# tsop_board.net
KiCad netlist of a schematic drawn in Altium Designer
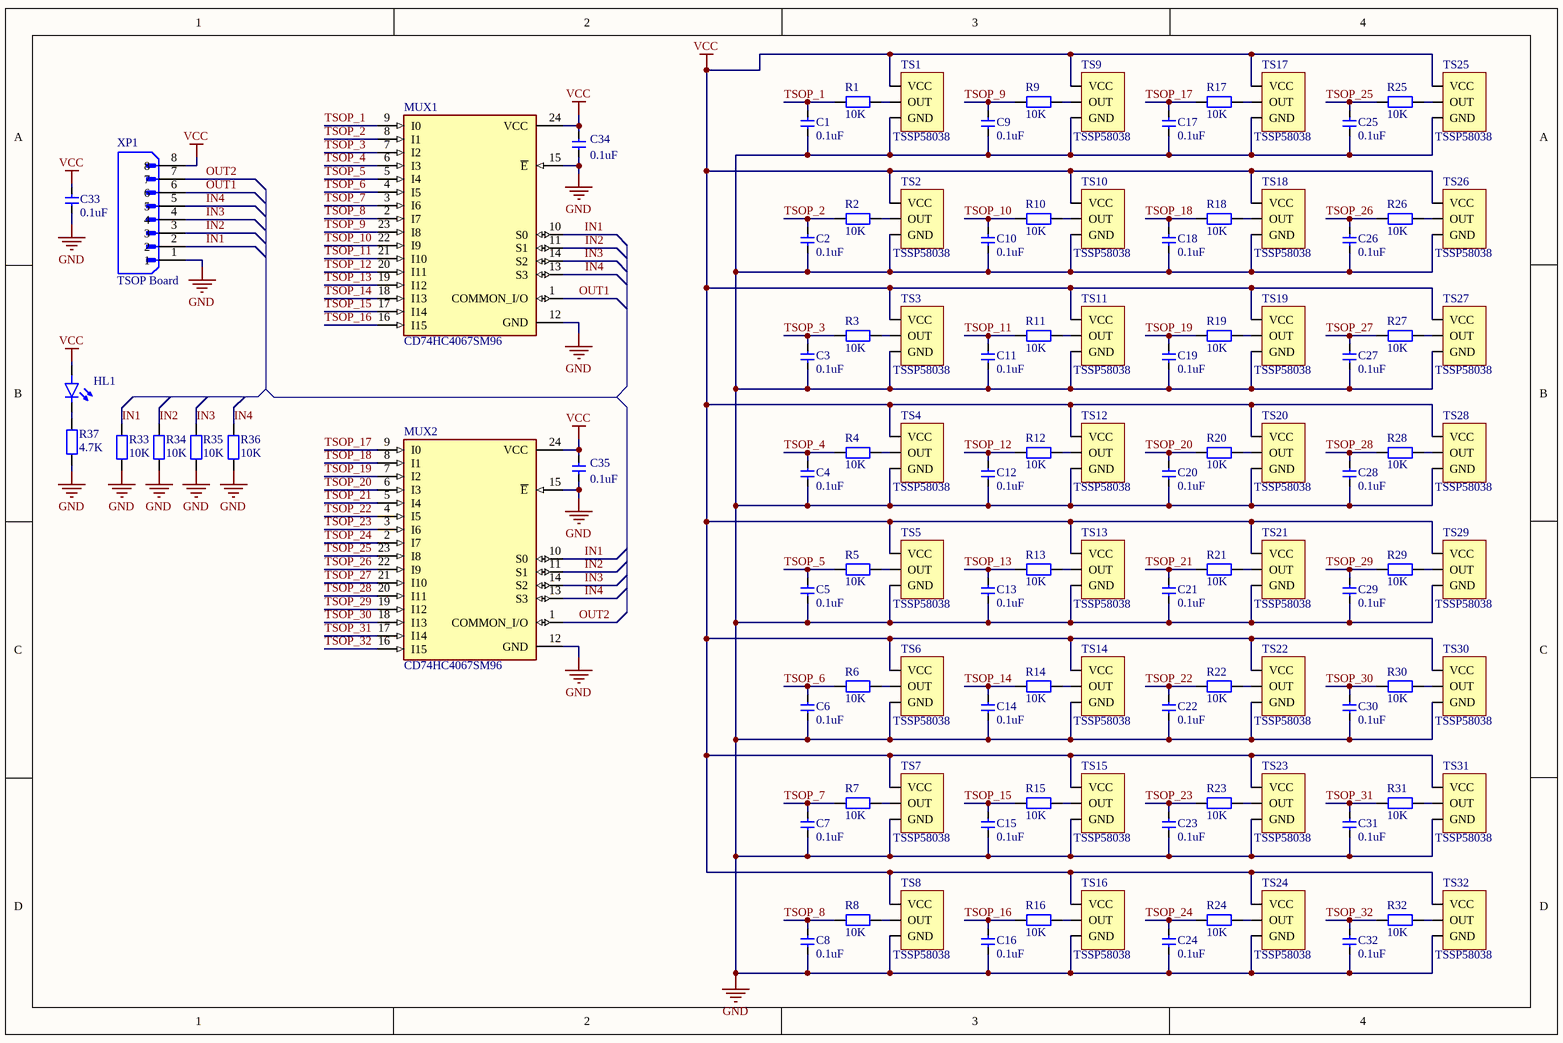
[diagram p0: tsop_board.SchDoc]

(export (version "E")
  (design (tool "Eeschema 10.0.6"))
  (components
    (comp (ref "C1")
      (value "0.1uF")
      (footprint "CAP0805")
      (description "Ceramic SMD Cap")
      (libsource (lib "Asterisk") (part "CAP Ceramic"))
    )
    (comp (ref "C2")
      (value "0.1uF")
      (footprint "CAP0805")
      (description "Ceramic SMD Cap")
      (libsource (lib "Asterisk") (part "CAP Ceramic"))
    )
    (comp (ref "C3")
      (value "0.1uF")
      (footprint "CAP0805")
      (description "Ceramic SMD Cap")
      (libsource (lib "Asterisk") (part "CAP Ceramic"))
    )
    (comp (ref "C4")
      (value "0.1uF")
      (footprint "CAP0805")
      (description "Ceramic SMD Cap")
      (libsource (lib "Asterisk") (part "CAP Ceramic"))
    )
    (comp (ref "C5")
      (value "0.1uF")
      (footprint "CAP0805")
      (description "Ceramic SMD Cap")
      (libsource (lib "Asterisk") (part "CAP Ceramic"))
    )
    (comp (ref "C6")
      (value "0.1uF")
      (footprint "CAP0805")
      (description "Ceramic SMD Cap")
      (libsource (lib "Asterisk") (part "CAP Ceramic"))
    )
    (comp (ref "C7")
      (value "0.1uF")
      (footprint "CAP0805")
      (description "Ceramic SMD Cap")
      (libsource (lib "Asterisk") (part "CAP Ceramic"))
    )
    (comp (ref "C8")
      (value "0.1uF")
      (footprint "CAP0805")
      (description "Ceramic SMD Cap")
      (libsource (lib "Asterisk") (part "CAP Ceramic"))
    )
    (comp (ref "C9")
      (value "0.1uF")
      (footprint "CAP0805")
      (description "Ceramic SMD Cap")
      (libsource (lib "Asterisk") (part "CAP Ceramic"))
    )
    (comp (ref "C10")
      (value "0.1uF")
      (footprint "CAP0805")
      (description "Ceramic SMD Cap")
      (libsource (lib "Asterisk") (part "CAP Ceramic"))
    )
    (comp (ref "C11")
      (value "0.1uF")
      (footprint "CAP0805")
      (description "Ceramic SMD Cap")
      (libsource (lib "Asterisk") (part "CAP Ceramic"))
    )
    (comp (ref "C12")
      (value "0.1uF")
      (footprint "CAP0805")
      (description "Ceramic SMD Cap")
      (libsource (lib "Asterisk") (part "CAP Ceramic"))
    )
    (comp (ref "C13")
      (value "0.1uF")
      (footprint "CAP0805")
      (description "Ceramic SMD Cap")
      (libsource (lib "Asterisk") (part "CAP Ceramic"))
    )
    (comp (ref "C14")
      (value "0.1uF")
      (footprint "CAP0805")
      (description "Ceramic SMD Cap")
      (libsource (lib "Asterisk") (part "CAP Ceramic"))
    )
    (comp (ref "C15")
      (value "0.1uF")
      (footprint "CAP0805")
      (description "Ceramic SMD Cap")
      (libsource (lib "Asterisk") (part "CAP Ceramic"))
    )
    (comp (ref "C16")
      (value "0.1uF")
      (footprint "CAP0805")
      (description "Ceramic SMD Cap")
      (libsource (lib "Asterisk") (part "CAP Ceramic"))
    )
    (comp (ref "C17")
      (value "0.1uF")
      (footprint "CAP0805")
      (description "Ceramic SMD Cap")
      (libsource (lib "Asterisk") (part "CAP Ceramic"))
    )
    (comp (ref "C18")
      (value "0.1uF")
      (footprint "CAP0805")
      (description "Ceramic SMD Cap")
      (libsource (lib "Asterisk") (part "CAP Ceramic"))
    )
    (comp (ref "C19")
      (value "0.1uF")
      (footprint "CAP0805")
      (description "Ceramic SMD Cap")
      (libsource (lib "Asterisk") (part "CAP Ceramic"))
    )
    (comp (ref "C20")
      (value "0.1uF")
      (footprint "CAP0805")
      (description "Ceramic SMD Cap")
      (libsource (lib "Asterisk") (part "CAP Ceramic"))
    )
    (comp (ref "C21")
      (value "0.1uF")
      (footprint "CAP0805")
      (description "Ceramic SMD Cap")
      (libsource (lib "Asterisk") (part "CAP Ceramic"))
    )
    (comp (ref "C22")
      (value "0.1uF")
      (footprint "CAP0805")
      (description "Ceramic SMD Cap")
      (libsource (lib "Asterisk") (part "CAP Ceramic"))
    )
    (comp (ref "C23")
      (value "0.1uF")
      (footprint "CAP0805")
      (description "Ceramic SMD Cap")
      (libsource (lib "Asterisk") (part "CAP Ceramic"))
    )
    (comp (ref "C24")
      (value "0.1uF")
      (footprint "CAP0805")
      (description "Ceramic SMD Cap")
      (libsource (lib "Asterisk") (part "CAP Ceramic"))
    )
    (comp (ref "C25")
      (value "0.1uF")
      (footprint "CAP0805")
      (description "Ceramic SMD Cap")
      (libsource (lib "Asterisk") (part "CAP Ceramic"))
    )
    (comp (ref "C26")
      (value "0.1uF")
      (footprint "CAP0805")
      (description "Ceramic SMD Cap")
      (libsource (lib "Asterisk") (part "CAP Ceramic"))
    )
    (comp (ref "C27")
      (value "0.1uF")
      (footprint "CAP0805")
      (description "Ceramic SMD Cap")
      (libsource (lib "Asterisk") (part "CAP Ceramic"))
    )
    (comp (ref "C28")
      (value "0.1uF")
      (footprint "CAP0805")
      (description "Ceramic SMD Cap")
      (libsource (lib "Asterisk") (part "CAP Ceramic"))
    )
    (comp (ref "C29")
      (value "0.1uF")
      (footprint "CAP0805")
      (description "Ceramic SMD Cap")
      (libsource (lib "Asterisk") (part "CAP Ceramic"))
    )
    (comp (ref "C30")
      (value "0.1uF")
      (footprint "CAP0805")
      (description "Ceramic SMD Cap")
      (libsource (lib "Asterisk") (part "CAP Ceramic"))
    )
    (comp (ref "C31")
      (value "0.1uF")
      (footprint "CAP0805")
      (description "Ceramic SMD Cap")
      (libsource (lib "Asterisk") (part "CAP Ceramic"))
    )
    (comp (ref "C32")
      (value "0.1uF")
      (footprint "CAP0805")
      (description "Ceramic SMD Cap")
      (libsource (lib "Asterisk") (part "CAP Ceramic"))
    )
    (comp (ref "C33")
      (value "0.1uF")
      (footprint "CAP0805")
      (description "Ceramic SMD Cap")
      (libsource (lib "Asterisk") (part "CAP Ceramic"))
    )
    (comp (ref "C34")
      (value "0.1uF")
      (footprint "CAP0805")
      (description "Ceramic SMD Cap")
      (libsource (lib "Asterisk") (part "CAP Ceramic"))
    )
    (comp (ref "C35")
      (value "0.1uF")
      (footprint "CAP0805")
      (description "Ceramic SMD Cap")
      (libsource (lib "Asterisk") (part "CAP Ceramic"))
    )
    (comp (ref "HL1")
      (value "VCC")
      (footprint "LED0603_GREEN")
      (description "LED smd")
      (libsource (lib "Asterisk") (part "LED"))
    )
    (comp (ref "MUX1")
      (value "CD74HC4067SM96")
      (footprint "SSOP-24")
      (description "16-channel multiplexer")
      (libsource (lib "Asterisk") (part "CD74HC4067SM96"))
    )
    (comp (ref "MUX2")
      (value "CD74HC4067SM96")
      (footprint "SSOP-24")
      (description "16-channel multiplexer")
      (libsource (lib "Asterisk") (part "CD74HC4067SM96"))
    )
    (comp (ref "R1")
      (value "10K")
      (footprint "RES0805")
      (description "RES smd")
      (libsource (lib "Asterisk") (part "RES"))
    )
    (comp (ref "R2")
      (value "10K")
      (footprint "RES0805")
      (description "RES smd")
      (libsource (lib "Asterisk") (part "RES"))
    )
    (comp (ref "R3")
      (value "10K")
      (footprint "RES0805")
      (description "RES smd")
      (libsource (lib "Asterisk") (part "RES"))
    )
    (comp (ref "R4")
      (value "10K")
      (footprint "RES0805")
      (description "RES smd")
      (libsource (lib "Asterisk") (part "RES"))
    )
    (comp (ref "R5")
      (value "10K")
      (footprint "RES0805")
      (description "RES smd")
      (libsource (lib "Asterisk") (part "RES"))
    )
    (comp (ref "R6")
      (value "10K")
      (footprint "RES0805")
      (description "RES smd")
      (libsource (lib "Asterisk") (part "RES"))
    )
    (comp (ref "R7")
      (value "10K")
      (footprint "RES0805")
      (description "RES smd")
      (libsource (lib "Asterisk") (part "RES"))
    )
    (comp (ref "R8")
      (value "10K")
      (footprint "RES0805")
      (description "RES smd")
      (libsource (lib "Asterisk") (part "RES"))
    )
    (comp (ref "R9")
      (value "10K")
      (footprint "RES0805")
      (description "RES smd")
      (libsource (lib "") (part "RES_1"))
    )
    (comp (ref "R10")
      (value "10K")
      (footprint "RES0805")
      (description "RES smd")
      (libsource (lib "") (part "RES_1"))
    )
    (comp (ref "R11")
      (value "10K")
      (footprint "RES0805")
      (description "RES smd")
      (libsource (lib "") (part "RES_1"))
    )
    (comp (ref "R12")
      (value "10K")
      (footprint "RES0805")
      (description "RES smd")
      (libsource (lib "") (part "RES_1"))
    )
    (comp (ref "R13")
      (value "10K")
      (footprint "RES0805")
      (description "RES smd")
      (libsource (lib "") (part "RES_1"))
    )
    (comp (ref "R14")
      (value "10K")
      (footprint "RES0805")
      (description "RES smd")
      (libsource (lib "") (part "RES_1"))
    )
    (comp (ref "R15")
      (value "10K")
      (footprint "RES0805")
      (description "RES smd")
      (libsource (lib "") (part "RES_1"))
    )
    (comp (ref "R16")
      (value "10K")
      (footprint "RES0805")
      (description "RES smd")
      (libsource (lib "") (part "RES_1"))
    )
    (comp (ref "R17")
      (value "10K")
      (footprint "RES0805")
      (description "RES smd")
      (libsource (lib "Asterisk") (part "RES"))
    )
    (comp (ref "R18")
      (value "10K")
      (footprint "RES0805")
      (description "RES smd")
      (libsource (lib "Asterisk") (part "RES"))
    )
    (comp (ref "R19")
      (value "10K")
      (footprint "RES0805")
      (description "RES smd")
      (libsource (lib "Asterisk") (part "RES"))
    )
    (comp (ref "R20")
      (value "10K")
      (footprint "RES0805")
      (description "RES smd")
      (libsource (lib "Asterisk") (part "RES"))
    )
    (comp (ref "R21")
      (value "10K")
      (footprint "RES0805")
      (description "RES smd")
      (libsource (lib "Asterisk") (part "RES"))
    )
    (comp (ref "R22")
      (value "10K")
      (footprint "RES0805")
      (description "RES smd")
      (libsource (lib "Asterisk") (part "RES"))
    )
    (comp (ref "R23")
      (value "10K")
      (footprint "RES0805")
      (description "RES smd")
      (libsource (lib "Asterisk") (part "RES"))
    )
    (comp (ref "R24")
      (value "10K")
      (footprint "RES0805")
      (description "RES smd")
      (libsource (lib "Asterisk") (part "RES"))
    )
    (comp (ref "R25")
      (value "10K")
      (footprint "RES0805")
      (description "RES smd")
      (libsource (lib "Asterisk") (part "RES"))
    )
    (comp (ref "R26")
      (value "10K")
      (footprint "RES0805")
      (description "RES smd")
      (libsource (lib "Asterisk") (part "RES"))
    )
    (comp (ref "R27")
      (value "10K")
      (footprint "RES0805")
      (description "RES smd")
      (libsource (lib "Asterisk") (part "RES"))
    )
    (comp (ref "R28")
      (value "10K")
      (footprint "RES0805")
      (description "RES smd")
      (libsource (lib "Asterisk") (part "RES"))
    )
    (comp (ref "R29")
      (value "10K")
      (footprint "RES0805")
      (description "RES smd")
      (libsource (lib "Asterisk") (part "RES"))
    )
    (comp (ref "R30")
      (value "10K")
      (footprint "RES0805")
      (description "RES smd")
      (libsource (lib "Asterisk") (part "RES"))
    )
    (comp (ref "R31")
      (value "10K")
      (footprint "RES0805")
      (description "RES smd")
      (libsource (lib "Asterisk") (part "RES"))
    )
    (comp (ref "R32")
      (value "10K")
      (footprint "RES0805")
      (description "RES smd")
      (libsource (lib "Asterisk") (part "RES"))
    )
    (comp (ref "R33")
      (value "10K")
      (footprint "RES0805")
      (description "RES smd")
      (libsource (lib "Asterisk") (part "RES"))
    )
    (comp (ref "R34")
      (value "10K")
      (footprint "RES0805")
      (description "RES smd")
      (libsource (lib "Asterisk") (part "RES"))
    )
    (comp (ref "R35")
      (value "10K")
      (footprint "RES0805")
      (description "RES smd")
      (libsource (lib "Asterisk") (part "RES"))
    )
    (comp (ref "R36")
      (value "10K")
      (footprint "RES0805")
      (description "RES smd")
      (libsource (lib "Asterisk") (part "RES"))
    )
    (comp (ref "R37")
      (value "4.7K")
      (footprint "RES0805")
      (description "RES smd")
      (libsource (lib "Asterisk") (part "RES"))
    )
    (comp (ref "TS1")
      (value "TSSP58038")
      (footprint "TSSP58038 (clear)")
      (description "TSOP TSSP58038")
      (libsource (lib "Asterisk") (part "TSSP58038"))
    )
    (comp (ref "TS2")
      (value "TSSP58038")
      (footprint "TSSP58038 (clear)")
      (description "TSOP TSSP58038")
      (libsource (lib "Asterisk") (part "TSSP58038"))
    )
    (comp (ref "TS3")
      (value "TSSP58038")
      (footprint "TSSP58038 (clear)")
      (description "TSOP TSSP58038")
      (libsource (lib "Asterisk") (part "TSSP58038"))
    )
    (comp (ref "TS4")
      (value "TSSP58038")
      (footprint "TSSP58038 (clear)")
      (description "TSOP TSSP58038")
      (libsource (lib "Asterisk") (part "TSSP58038"))
    )
    (comp (ref "TS5")
      (value "TSSP58038")
      (footprint "TSSP58038 (clear)")
      (description "TSOP TSSP58038")
      (libsource (lib "Asterisk") (part "TSSP58038"))
    )
    (comp (ref "TS6")
      (value "TSSP58038")
      (footprint "TSSP58038 (clear)")
      (description "TSOP TSSP58038")
      (libsource (lib "Asterisk") (part "TSSP58038"))
    )
    (comp (ref "TS7")
      (value "TSSP58038")
      (footprint "TSSP58038 (clear)")
      (description "TSOP TSSP58038")
      (libsource (lib "Asterisk") (part "TSSP58038"))
    )
    (comp (ref "TS8")
      (value "TSSP58038")
      (footprint "TSSP58038 (clear)")
      (description "TSOP TSSP58038")
      (libsource (lib "Asterisk") (part "TSSP58038"))
    )
    (comp (ref "TS9")
      (value "TSSP58038")
      (footprint "TSSP58038 (clear)")
      (description "TSOP TSSP58038")
      (libsource (lib "Asterisk") (part "TSSP58038"))
    )
    (comp (ref "TS10")
      (value "TSSP58038")
      (footprint "TSSP58038 (clear)")
      (description "TSOP TSSP58038")
      (libsource (lib "Asterisk") (part "TSSP58038"))
    )
    (comp (ref "TS11")
      (value "TSSP58038")
      (footprint "TSSP58038 (clear)")
      (description "TSOP TSSP58038")
      (libsource (lib "Asterisk") (part "TSSP58038"))
    )
    (comp (ref "TS12")
      (value "TSSP58038")
      (footprint "TSSP58038 (clear)")
      (description "TSOP TSSP58038")
      (libsource (lib "Asterisk") (part "TSSP58038"))
    )
    (comp (ref "TS13")
      (value "TSSP58038")
      (footprint "TSSP58038 (clear)")
      (description "TSOP TSSP58038")
      (libsource (lib "Asterisk") (part "TSSP58038"))
    )
    (comp (ref "TS14")
      (value "TSSP58038")
      (footprint "TSSP58038 (clear)")
      (description "TSOP TSSP58038")
      (libsource (lib "Asterisk") (part "TSSP58038"))
    )
    (comp (ref "TS15")
      (value "TSSP58038")
      (footprint "TSSP58038 (clear)")
      (description "TSOP TSSP58038")
      (libsource (lib "Asterisk") (part "TSSP58038"))
    )
    (comp (ref "TS16")
      (value "TSSP58038")
      (footprint "TSSP58038 (clear)")
      (description "TSOP TSSP58038")
      (libsource (lib "Asterisk") (part "TSSP58038"))
    )
    (comp (ref "TS17")
      (value "TSSP58038")
      (footprint "TSSP58038 (clear)")
      (description "TSOP TSSP58038")
      (libsource (lib "Asterisk") (part "TSSP58038"))
    )
    (comp (ref "TS18")
      (value "TSSP58038")
      (footprint "TSSP58038 (clear)")
      (description "TSOP TSSP58038")
      (libsource (lib "Asterisk") (part "TSSP58038"))
    )
    (comp (ref "TS19")
      (value "TSSP58038")
      (footprint "TSSP58038 (clear)")
      (description "TSOP TSSP58038")
      (libsource (lib "Asterisk") (part "TSSP58038"))
    )
    (comp (ref "TS20")
      (value "TSSP58038")
      (footprint "TSSP58038 (clear)")
      (description "TSOP TSSP58038")
      (libsource (lib "Asterisk") (part "TSSP58038"))
    )
    (comp (ref "TS21")
      (value "TSSP58038")
      (footprint "TSSP58038 (clear)")
      (description "TSOP TSSP58038")
      (libsource (lib "Asterisk") (part "TSSP58038"))
    )
    (comp (ref "TS22")
      (value "TSSP58038")
      (footprint "TSSP58038 (clear)")
      (description "TSOP TSSP58038")
      (libsource (lib "Asterisk") (part "TSSP58038"))
    )
    (comp (ref "TS23")
      (value "TSSP58038")
      (footprint "TSSP58038 (clear)")
      (description "TSOP TSSP58038")
      (libsource (lib "Asterisk") (part "TSSP58038"))
    )
    (comp (ref "TS24")
      (value "TSSP58038")
      (footprint "TSSP58038 (clear)")
      (description "TSOP TSSP58038")
      (libsource (lib "Asterisk") (part "TSSP58038"))
    )
    (comp (ref "TS25")
      (value "TSSP58038")
      (footprint "TSSP58038 (clear)")
      (description "TSOP TSSP58038")
      (libsource (lib "Asterisk") (part "TSSP58038"))
    )
    (comp (ref "TS26")
      (value "TSSP58038")
      (footprint "TSSP58038 (clear)")
      (description "TSOP TSSP58038")
      (libsource (lib "Asterisk") (part "TSSP58038"))
    )
    (comp (ref "TS27")
      (value "TSSP58038")
      (footprint "TSSP58038 (clear)")
      (description "TSOP TSSP58038")
      (libsource (lib "Asterisk") (part "TSSP58038"))
    )
    (comp (ref "TS28")
      (value "TSSP58038")
      (footprint "TSSP58038 (clear)")
      (description "TSOP TSSP58038")
      (libsource (lib "Asterisk") (part "TSSP58038"))
    )
    (comp (ref "TS29")
      (value "TSSP58038")
      (footprint "TSSP58038 (clear)")
      (description "TSOP TSSP58038")
      (libsource (lib "Asterisk") (part "TSSP58038"))
    )
    (comp (ref "TS30")
      (value "TSSP58038")
      (footprint "TSSP58038 (clear)")
      (description "TSOP TSSP58038")
      (libsource (lib "Asterisk") (part "TSSP58038"))
    )
    (comp (ref "TS31")
      (value "TSSP58038")
      (footprint "TSSP58038 (clear)")
      (description "TSOP TSSP58038")
      (libsource (lib "Asterisk") (part "TSSP58038"))
    )
    (comp (ref "TS32")
      (value "TSSP58038")
      (footprint "TSSP58038 (clear)")
      (description "TSOP TSSP58038")
      (libsource (lib "Asterisk") (part "TSSP58038"))
    )
    (comp (ref "XP1")
      (value "TSOP Board")
      (footprint "JST_XH-8")
      (description "JST_B8B-XH-A(LF)(SN)")
      (libsource (lib "Asterisk") (part "JST-XH-8"))
    )
  )
  (nets
    (net (code "1") (name "/IN1") (class "Default")
      (node (ref "MUX1") (pin "10") (pinfunction "S0_10") (pintype "bidirectional"))
      (node (ref "MUX2") (pin "10") (pinfunction "S0_10") (pintype "bidirectional"))
      (node (ref "R33") (pin "2") (pinfunction "2_2") (pintype "passive"))
      (node (ref "XP1") (pin "2") (pinfunction "2_2") (pintype "passive"))
    )
    (net (code "2") (name "/IN2") (class "Default")
      (node (ref "MUX1") (pin "11") (pinfunction "S1_11") (pintype "bidirectional"))
      (node (ref "MUX2") (pin "11") (pinfunction "S1_11") (pintype "bidirectional"))
      (node (ref "R34") (pin "2") (pinfunction "2_2") (pintype "passive"))
      (node (ref "XP1") (pin "3") (pinfunction "3_3") (pintype "passive"))
    )
    (net (code "3") (name "/IN3") (class "Default")
      (node (ref "MUX1") (pin "14") (pinfunction "S2_14") (pintype "bidirectional"))
      (node (ref "MUX2") (pin "14") (pinfunction "S2_14") (pintype "bidirectional"))
      (node (ref "R35") (pin "2") (pinfunction "2_2") (pintype "passive"))
      (node (ref "XP1") (pin "4") (pinfunction "4_4") (pintype "passive"))
    )
    (net (code "4") (name "/IN4") (class "Default")
      (node (ref "MUX1") (pin "13") (pinfunction "S3_13") (pintype "bidirectional"))
      (node (ref "MUX2") (pin "13") (pinfunction "S3_13") (pintype "bidirectional"))
      (node (ref "R36") (pin "2") (pinfunction "2_2") (pintype "passive"))
      (node (ref "XP1") (pin "5") (pinfunction "5_5") (pintype "passive"))
    )
    (net (code "5") (name "/OUT1") (class "Default")
      (node (ref "MUX1") (pin "1") (pinfunction "COMMON_I/O_1") (pintype "bidirectional"))
      (node (ref "XP1") (pin "6") (pinfunction "6_6") (pintype "passive"))
    )
    (net (code "6") (name "/OUT2") (class "Default")
      (node (ref "MUX2") (pin "1") (pinfunction "COMMON_I/O_1") (pintype "bidirectional"))
      (node (ref "XP1") (pin "7") (pinfunction "7_7") (pintype "passive"))
    )
    (net (code "7") (name "/TSOP_1") (class "Default")
      (node (ref "C1") (pin "2") (pinfunction "2_2") (pintype "passive"))
      (node (ref "MUX1") (pin "9") (pinfunction "I0_9") (pintype "input"))
      (node (ref "R1") (pin "1") (pinfunction "1_1") (pintype "passive"))
    )
    (net (code "8") (name "/TSOP_2") (class "Default")
      (node (ref "C2") (pin "2") (pinfunction "2_2") (pintype "passive"))
      (node (ref "MUX1") (pin "8") (pinfunction "I1_8") (pintype "input"))
      (node (ref "R2") (pin "1") (pinfunction "1_1") (pintype "passive"))
    )
    (net (code "9") (name "/TSOP_3") (class "Default")
      (node (ref "C3") (pin "2") (pinfunction "2_2") (pintype "passive"))
      (node (ref "MUX1") (pin "7") (pinfunction "I2_7") (pintype "input"))
      (node (ref "R3") (pin "1") (pinfunction "1_1") (pintype "passive"))
    )
    (net (code "10") (name "/TSOP_4") (class "Default")
      (node (ref "C4") (pin "2") (pinfunction "2_2") (pintype "passive"))
      (node (ref "MUX1") (pin "6") (pinfunction "I3_6") (pintype "input"))
      (node (ref "R4") (pin "1") (pinfunction "1_1") (pintype "passive"))
    )
    (net (code "11") (name "/TSOP_5") (class "Default")
      (node (ref "C5") (pin "2") (pinfunction "2_2") (pintype "passive"))
      (node (ref "MUX1") (pin "5") (pinfunction "I4_5") (pintype "input"))
      (node (ref "R5") (pin "1") (pinfunction "1_1") (pintype "passive"))
    )
    (net (code "12") (name "/TSOP_6") (class "Default")
      (node (ref "C6") (pin "2") (pinfunction "2_2") (pintype "passive"))
      (node (ref "MUX1") (pin "4") (pinfunction "I5_4") (pintype "input"))
      (node (ref "R6") (pin "1") (pinfunction "1_1") (pintype "passive"))
    )
    (net (code "13") (name "/TSOP_7") (class "Default")
      (node (ref "C7") (pin "2") (pinfunction "2_2") (pintype "passive"))
      (node (ref "MUX1") (pin "3") (pinfunction "I6_3") (pintype "input"))
      (node (ref "R7") (pin "1") (pinfunction "1_1") (pintype "passive"))
    )
    (net (code "14") (name "/TSOP_8") (class "Default")
      (node (ref "C8") (pin "2") (pinfunction "2_2") (pintype "passive"))
      (node (ref "MUX1") (pin "2") (pinfunction "I7_2") (pintype "input"))
      (node (ref "R8") (pin "1") (pinfunction "1_1") (pintype "passive"))
    )
    (net (code "15") (name "/TSOP_9") (class "Default")
      (node (ref "C9") (pin "2") (pinfunction "2_2") (pintype "passive"))
      (node (ref "MUX1") (pin "23") (pinfunction "I8_23") (pintype "input"))
      (node (ref "R9") (pin "1") (pinfunction "1_1") (pintype "passive"))
    )
    (net (code "16") (name "/TSOP_10") (class "Default")
      (node (ref "C10") (pin "2") (pinfunction "2_2") (pintype "passive"))
      (node (ref "MUX1") (pin "22") (pinfunction "I9_22") (pintype "input"))
      (node (ref "R10") (pin "1") (pinfunction "1_1") (pintype "passive"))
    )
    (net (code "17") (name "/TSOP_11") (class "Default")
      (node (ref "C11") (pin "2") (pinfunction "2_2") (pintype "passive"))
      (node (ref "MUX1") (pin "21") (pinfunction "I10_21") (pintype "input"))
      (node (ref "R11") (pin "1") (pinfunction "1_1") (pintype "passive"))
    )
    (net (code "18") (name "/TSOP_12") (class "Default")
      (node (ref "C12") (pin "2") (pinfunction "2_2") (pintype "passive"))
      (node (ref "MUX1") (pin "20") (pinfunction "I11_20") (pintype "input"))
      (node (ref "R12") (pin "1") (pinfunction "1_1") (pintype "passive"))
    )
    (net (code "19") (name "/TSOP_13") (class "Default")
      (node (ref "C13") (pin "2") (pinfunction "2_2") (pintype "passive"))
      (node (ref "MUX1") (pin "19") (pinfunction "I12_19") (pintype "input"))
      (node (ref "R13") (pin "1") (pinfunction "1_1") (pintype "passive"))
    )
    (net (code "20") (name "/TSOP_14") (class "Default")
      (node (ref "C14") (pin "2") (pinfunction "2_2") (pintype "passive"))
      (node (ref "MUX1") (pin "18") (pinfunction "I13_18") (pintype "input"))
      (node (ref "R14") (pin "1") (pinfunction "1_1") (pintype "passive"))
    )
    (net (code "21") (name "/TSOP_15") (class "Default")
      (node (ref "C15") (pin "2") (pinfunction "2_2") (pintype "passive"))
      (node (ref "MUX1") (pin "17") (pinfunction "I14_17") (pintype "input"))
      (node (ref "R15") (pin "1") (pinfunction "1_1") (pintype "passive"))
    )
    (net (code "22") (name "/TSOP_16") (class "Default")
      (node (ref "C16") (pin "2") (pinfunction "2_2") (pintype "passive"))
      (node (ref "MUX1") (pin "16") (pinfunction "I15_16") (pintype "input"))
      (node (ref "R16") (pin "1") (pinfunction "1_1") (pintype "passive"))
    )
    (net (code "23") (name "/TSOP_17") (class "Default")
      (node (ref "C17") (pin "2") (pinfunction "2_2") (pintype "passive"))
      (node (ref "MUX2") (pin "9") (pinfunction "I0_9") (pintype "input"))
      (node (ref "R17") (pin "1") (pinfunction "1_1") (pintype "passive"))
    )
    (net (code "24") (name "/TSOP_18") (class "Default")
      (node (ref "C18") (pin "2") (pinfunction "2_2") (pintype "passive"))
      (node (ref "MUX2") (pin "8") (pinfunction "I1_8") (pintype "input"))
      (node (ref "R18") (pin "1") (pinfunction "1_1") (pintype "passive"))
    )
    (net (code "25") (name "/TSOP_19") (class "Default")
      (node (ref "C19") (pin "2") (pinfunction "2_2") (pintype "passive"))
      (node (ref "MUX2") (pin "7") (pinfunction "I2_7") (pintype "input"))
      (node (ref "R19") (pin "1") (pinfunction "1_1") (pintype "passive"))
    )
    (net (code "26") (name "/TSOP_20") (class "Default")
      (node (ref "C20") (pin "2") (pinfunction "2_2") (pintype "passive"))
      (node (ref "MUX2") (pin "6") (pinfunction "I3_6") (pintype "input"))
      (node (ref "R20") (pin "1") (pinfunction "1_1") (pintype "passive"))
    )
    (net (code "27") (name "/TSOP_21") (class "Default")
      (node (ref "C21") (pin "2") (pinfunction "2_2") (pintype "passive"))
      (node (ref "MUX2") (pin "5") (pinfunction "I4_5") (pintype "input"))
      (node (ref "R21") (pin "1") (pinfunction "1_1") (pintype "passive"))
    )
    (net (code "28") (name "/TSOP_22") (class "Default")
      (node (ref "C22") (pin "2") (pinfunction "2_2") (pintype "passive"))
      (node (ref "MUX2") (pin "4") (pinfunction "I5_4") (pintype "input"))
      (node (ref "R22") (pin "1") (pinfunction "1_1") (pintype "passive"))
    )
    (net (code "29") (name "/TSOP_23") (class "Default")
      (node (ref "C23") (pin "2") (pinfunction "2_2") (pintype "passive"))
      (node (ref "MUX2") (pin "3") (pinfunction "I6_3") (pintype "input"))
      (node (ref "R23") (pin "1") (pinfunction "1_1") (pintype "passive"))
    )
    (net (code "30") (name "/TSOP_24") (class "Default")
      (node (ref "C24") (pin "2") (pinfunction "2_2") (pintype "passive"))
      (node (ref "MUX2") (pin "2") (pinfunction "I7_2") (pintype "input"))
      (node (ref "R24") (pin "1") (pinfunction "1_1") (pintype "passive"))
    )
    (net (code "31") (name "/TSOP_25") (class "Default")
      (node (ref "C25") (pin "2") (pinfunction "2_2") (pintype "passive"))
      (node (ref "MUX2") (pin "23") (pinfunction "I8_23") (pintype "input"))
      (node (ref "R25") (pin "1") (pinfunction "1_1") (pintype "passive"))
    )
    (net (code "32") (name "/TSOP_26") (class "Default")
      (node (ref "C26") (pin "2") (pinfunction "2_2") (pintype "passive"))
      (node (ref "MUX2") (pin "22") (pinfunction "I9_22") (pintype "input"))
      (node (ref "R26") (pin "1") (pinfunction "1_1") (pintype "passive"))
    )
    (net (code "33") (name "/TSOP_27") (class "Default")
      (node (ref "C27") (pin "2") (pinfunction "2_2") (pintype "passive"))
      (node (ref "MUX2") (pin "21") (pinfunction "I10_21") (pintype "input"))
      (node (ref "R27") (pin "1") (pinfunction "1_1") (pintype "passive"))
    )
    (net (code "34") (name "/TSOP_28") (class "Default")
      (node (ref "C28") (pin "2") (pinfunction "2_2") (pintype "passive"))
      (node (ref "MUX2") (pin "20") (pinfunction "I11_20") (pintype "input"))
      (node (ref "R28") (pin "1") (pinfunction "1_1") (pintype "passive"))
    )
    (net (code "35") (name "/TSOP_29") (class "Default")
      (node (ref "C29") (pin "2") (pinfunction "2_2") (pintype "passive"))
      (node (ref "MUX2") (pin "19") (pinfunction "I12_19") (pintype "input"))
      (node (ref "R29") (pin "1") (pinfunction "1_1") (pintype "passive"))
    )
    (net (code "36") (name "/TSOP_30") (class "Default")
      (node (ref "C30") (pin "2") (pinfunction "2_2") (pintype "passive"))
      (node (ref "MUX2") (pin "18") (pinfunction "I13_18") (pintype "input"))
      (node (ref "R30") (pin "1") (pinfunction "1_1") (pintype "passive"))
    )
    (net (code "37") (name "/TSOP_31") (class "Default")
      (node (ref "C31") (pin "2") (pinfunction "2_2") (pintype "passive"))
      (node (ref "MUX2") (pin "17") (pinfunction "I14_17") (pintype "input"))
      (node (ref "R31") (pin "1") (pinfunction "1_1") (pintype "passive"))
    )
    (net (code "38") (name "/TSOP_32") (class "Default")
      (node (ref "C32") (pin "2") (pinfunction "2_2") (pintype "passive"))
      (node (ref "MUX2") (pin "16") (pinfunction "I15_16") (pintype "input"))
      (node (ref "R32") (pin "1") (pinfunction "1_1") (pintype "passive"))
    )
    (net (code "39") (name "GND") (class "Default")
      (node (ref "C1") (pin "1") (pinfunction "1_1") (pintype "passive"))
      (node (ref "C10") (pin "1") (pinfunction "1_1") (pintype "passive"))
      (node (ref "C11") (pin "1") (pinfunction "1_1") (pintype "passive"))
      (node (ref "C12") (pin "1") (pinfunction "1_1") (pintype "passive"))
      (node (ref "C13") (pin "1") (pinfunction "1_1") (pintype "passive"))
      (node (ref "C14") (pin "1") (pinfunction "1_1") (pintype "passive"))
      (node (ref "C15") (pin "1") (pinfunction "1_1") (pintype "passive"))
      (node (ref "C16") (pin "1") (pinfunction "1_1") (pintype "passive"))
      (node (ref "C17") (pin "1") (pinfunction "1_1") (pintype "passive"))
      (node (ref "C18") (pin "1") (pinfunction "1_1") (pintype "passive"))
      (node (ref "C19") (pin "1") (pinfunction "1_1") (pintype "passive"))
      (node (ref "C2") (pin "1") (pinfunction "1_1") (pintype "passive"))
      (node (ref "C20") (pin "1") (pinfunction "1_1") (pintype "passive"))
      (node (ref "C21") (pin "1") (pinfunction "1_1") (pintype "passive"))
      (node (ref "C22") (pin "1") (pinfunction "1_1") (pintype "passive"))
      (node (ref "C23") (pin "1") (pinfunction "1_1") (pintype "passive"))
      (node (ref "C24") (pin "1") (pinfunction "1_1") (pintype "passive"))
      (node (ref "C25") (pin "1") (pinfunction "1_1") (pintype "passive"))
      (node (ref "C26") (pin "1") (pinfunction "1_1") (pintype "passive"))
      (node (ref "C27") (pin "1") (pinfunction "1_1") (pintype "passive"))
      (node (ref "C28") (pin "1") (pinfunction "1_1") (pintype "passive"))
      (node (ref "C29") (pin "1") (pinfunction "1_1") (pintype "passive"))
      (node (ref "C3") (pin "1") (pinfunction "1_1") (pintype "passive"))
      (node (ref "C30") (pin "1") (pinfunction "1_1") (pintype "passive"))
      (node (ref "C31") (pin "1") (pinfunction "1_1") (pintype "passive"))
      (node (ref "C32") (pin "1") (pinfunction "1_1") (pintype "passive"))
      (node (ref "C33") (pin "1") (pinfunction "1_1") (pintype "passive"))
      (node (ref "C34") (pin "1") (pinfunction "1_1") (pintype "passive"))
      (node (ref "C35") (pin "1") (pinfunction "1_1") (pintype "passive"))
      (node (ref "C4") (pin "1") (pinfunction "1_1") (pintype "passive"))
      (node (ref "C5") (pin "1") (pinfunction "1_1") (pintype "passive"))
      (node (ref "C6") (pin "1") (pinfunction "1_1") (pintype "passive"))
      (node (ref "C7") (pin "1") (pinfunction "1_1") (pintype "passive"))
      (node (ref "C8") (pin "1") (pinfunction "1_1") (pintype "passive"))
      (node (ref "C9") (pin "1") (pinfunction "1_1") (pintype "passive"))
      (node (ref "MUX1") (pin "12") (pinfunction "GND_12") (pintype "power_in"))
      (node (ref "MUX1") (pin "15") (pinfunction "~{E}_15") (pintype "input"))
      (node (ref "MUX2") (pin "12") (pinfunction "GND_12") (pintype "power_in"))
      (node (ref "MUX2") (pin "15") (pinfunction "~{E}_15") (pintype "input"))
      (node (ref "R33") (pin "1") (pinfunction "1_1") (pintype "passive"))
      (node (ref "R34") (pin "1") (pinfunction "1_1") (pintype "passive"))
      (node (ref "R35") (pin "1") (pinfunction "1_1") (pintype "passive"))
      (node (ref "R36") (pin "1") (pinfunction "1_1") (pintype "passive"))
      (node (ref "R37") (pin "1") (pinfunction "1_1") (pintype "passive"))
      (node (ref "TS1") (pin "2") (pinfunction "GND_2") (pintype "passive"))
      (node (ref "TS10") (pin "2") (pinfunction "GND_2") (pintype "passive"))
      (node (ref "TS11") (pin "2") (pinfunction "GND_2") (pintype "passive"))
      (node (ref "TS12") (pin "2") (pinfunction "GND_2") (pintype "passive"))
      (node (ref "TS13") (pin "2") (pinfunction "GND_2") (pintype "passive"))
      (node (ref "TS14") (pin "2") (pinfunction "GND_2") (pintype "passive"))
      (node (ref "TS15") (pin "2") (pinfunction "GND_2") (pintype "passive"))
      (node (ref "TS16") (pin "2") (pinfunction "GND_2") (pintype "passive"))
      (node (ref "TS17") (pin "2") (pinfunction "GND_2") (pintype "passive"))
      (node (ref "TS18") (pin "2") (pinfunction "GND_2") (pintype "passive"))
      (node (ref "TS19") (pin "2") (pinfunction "GND_2") (pintype "passive"))
      (node (ref "TS2") (pin "2") (pinfunction "GND_2") (pintype "passive"))
      (node (ref "TS20") (pin "2") (pinfunction "GND_2") (pintype "passive"))
      (node (ref "TS21") (pin "2") (pinfunction "GND_2") (pintype "passive"))
      (node (ref "TS22") (pin "2") (pinfunction "GND_2") (pintype "passive"))
      (node (ref "TS23") (pin "2") (pinfunction "GND_2") (pintype "passive"))
      (node (ref "TS24") (pin "2") (pinfunction "GND_2") (pintype "passive"))
      (node (ref "TS25") (pin "2") (pinfunction "GND_2") (pintype "passive"))
      (node (ref "TS26") (pin "2") (pinfunction "GND_2") (pintype "passive"))
      (node (ref "TS27") (pin "2") (pinfunction "GND_2") (pintype "passive"))
      (node (ref "TS28") (pin "2") (pinfunction "GND_2") (pintype "passive"))
      (node (ref "TS29") (pin "2") (pinfunction "GND_2") (pintype "passive"))
      (node (ref "TS3") (pin "2") (pinfunction "GND_2") (pintype "passive"))
      (node (ref "TS30") (pin "2") (pinfunction "GND_2") (pintype "passive"))
      (node (ref "TS31") (pin "2") (pinfunction "GND_2") (pintype "passive"))
      (node (ref "TS32") (pin "2") (pinfunction "GND_2") (pintype "passive"))
      (node (ref "TS4") (pin "2") (pinfunction "GND_2") (pintype "passive"))
      (node (ref "TS5") (pin "2") (pinfunction "GND_2") (pintype "passive"))
      (node (ref "TS6") (pin "2") (pinfunction "GND_2") (pintype "passive"))
      (node (ref "TS7") (pin "2") (pinfunction "GND_2") (pintype "passive"))
      (node (ref "TS8") (pin "2") (pinfunction "GND_2") (pintype "passive"))
      (node (ref "TS9") (pin "2") (pinfunction "GND_2") (pintype "passive"))
      (node (ref "XP1") (pin "1") (pinfunction "1_1") (pintype "passive"))
    )
    (net (code "40") (name "Net-(HL1-K)") (class "Default")
      (node (ref "HL1") (pin "1") (pinfunction "K_1") (pintype "passive"))
      (node (ref "R37") (pin "2") (pinfunction "2_2") (pintype "passive"))
    )
    (net (code "41") (name "Net-(TS1-OUT)") (class "Default")
      (node (ref "R1") (pin "2") (pinfunction "2_2") (pintype "passive"))
      (node (ref "TS1") (pin "3") (pinfunction "OUT_3") (pintype "passive"))
    )
    (net (code "42") (name "Net-(TS2-OUT)") (class "Default")
      (node (ref "R2") (pin "2") (pinfunction "2_2") (pintype "passive"))
      (node (ref "TS2") (pin "3") (pinfunction "OUT_3") (pintype "passive"))
    )
    (net (code "43") (name "Net-(TS3-OUT)") (class "Default")
      (node (ref "R3") (pin "2") (pinfunction "2_2") (pintype "passive"))
      (node (ref "TS3") (pin "3") (pinfunction "OUT_3") (pintype "passive"))
    )
    (net (code "44") (name "Net-(TS4-OUT)") (class "Default")
      (node (ref "R4") (pin "2") (pinfunction "2_2") (pintype "passive"))
      (node (ref "TS4") (pin "3") (pinfunction "OUT_3") (pintype "passive"))
    )
    (net (code "45") (name "Net-(TS5-OUT)") (class "Default")
      (node (ref "R5") (pin "2") (pinfunction "2_2") (pintype "passive"))
      (node (ref "TS5") (pin "3") (pinfunction "OUT_3") (pintype "passive"))
    )
    (net (code "46") (name "Net-(TS6-OUT)") (class "Default")
      (node (ref "R6") (pin "2") (pinfunction "2_2") (pintype "passive"))
      (node (ref "TS6") (pin "3") (pinfunction "OUT_3") (pintype "passive"))
    )
    (net (code "47") (name "Net-(TS7-OUT)") (class "Default")
      (node (ref "R7") (pin "2") (pinfunction "2_2") (pintype "passive"))
      (node (ref "TS7") (pin "3") (pinfunction "OUT_3") (pintype "passive"))
    )
    (net (code "48") (name "Net-(TS8-OUT)") (class "Default")
      (node (ref "R8") (pin "2") (pinfunction "2_2") (pintype "passive"))
      (node (ref "TS8") (pin "3") (pinfunction "OUT_3") (pintype "passive"))
    )
    (net (code "49") (name "Net-(TS9-OUT)") (class "Default")
      (node (ref "R9") (pin "2") (pinfunction "2_2") (pintype "passive"))
      (node (ref "TS9") (pin "3") (pinfunction "OUT_3") (pintype "passive"))
    )
    (net (code "50") (name "Net-(TS10-OUT)") (class "Default")
      (node (ref "R10") (pin "2") (pinfunction "2_2") (pintype "passive"))
      (node (ref "TS10") (pin "3") (pinfunction "OUT_3") (pintype "passive"))
    )
    (net (code "51") (name "Net-(TS11-OUT)") (class "Default")
      (node (ref "R11") (pin "2") (pinfunction "2_2") (pintype "passive"))
      (node (ref "TS11") (pin "3") (pinfunction "OUT_3") (pintype "passive"))
    )
    (net (code "52") (name "Net-(TS12-OUT)") (class "Default")
      (node (ref "R12") (pin "2") (pinfunction "2_2") (pintype "passive"))
      (node (ref "TS12") (pin "3") (pinfunction "OUT_3") (pintype "passive"))
    )
    (net (code "53") (name "Net-(TS13-OUT)") (class "Default")
      (node (ref "R13") (pin "2") (pinfunction "2_2") (pintype "passive"))
      (node (ref "TS13") (pin "3") (pinfunction "OUT_3") (pintype "passive"))
    )
    (net (code "54") (name "Net-(TS14-OUT)") (class "Default")
      (node (ref "R14") (pin "2") (pinfunction "2_2") (pintype "passive"))
      (node (ref "TS14") (pin "3") (pinfunction "OUT_3") (pintype "passive"))
    )
    (net (code "55") (name "Net-(TS15-OUT)") (class "Default")
      (node (ref "R15") (pin "2") (pinfunction "2_2") (pintype "passive"))
      (node (ref "TS15") (pin "3") (pinfunction "OUT_3") (pintype "passive"))
    )
    (net (code "56") (name "Net-(TS16-OUT)") (class "Default")
      (node (ref "R16") (pin "2") (pinfunction "2_2") (pintype "passive"))
      (node (ref "TS16") (pin "3") (pinfunction "OUT_3") (pintype "passive"))
    )
    (net (code "57") (name "Net-(TS17-OUT)") (class "Default")
      (node (ref "R17") (pin "2") (pinfunction "2_2") (pintype "passive"))
      (node (ref "TS17") (pin "3") (pinfunction "OUT_3") (pintype "passive"))
    )
    (net (code "58") (name "Net-(TS18-OUT)") (class "Default")
      (node (ref "R18") (pin "2") (pinfunction "2_2") (pintype "passive"))
      (node (ref "TS18") (pin "3") (pinfunction "OUT_3") (pintype "passive"))
    )
    (net (code "59") (name "Net-(TS19-OUT)") (class "Default")
      (node (ref "R19") (pin "2") (pinfunction "2_2") (pintype "passive"))
      (node (ref "TS19") (pin "3") (pinfunction "OUT_3") (pintype "passive"))
    )
    (net (code "60") (name "Net-(TS20-OUT)") (class "Default")
      (node (ref "R20") (pin "2") (pinfunction "2_2") (pintype "passive"))
      (node (ref "TS20") (pin "3") (pinfunction "OUT_3") (pintype "passive"))
    )
    (net (code "61") (name "Net-(TS21-OUT)") (class "Default")
      (node (ref "R21") (pin "2") (pinfunction "2_2") (pintype "passive"))
      (node (ref "TS21") (pin "3") (pinfunction "OUT_3") (pintype "passive"))
    )
    (net (code "62") (name "Net-(TS22-OUT)") (class "Default")
      (node (ref "R22") (pin "2") (pinfunction "2_2") (pintype "passive"))
      (node (ref "TS22") (pin "3") (pinfunction "OUT_3") (pintype "passive"))
    )
    (net (code "63") (name "Net-(TS23-OUT)") (class "Default")
      (node (ref "R23") (pin "2") (pinfunction "2_2") (pintype "passive"))
      (node (ref "TS23") (pin "3") (pinfunction "OUT_3") (pintype "passive"))
    )
    (net (code "64") (name "Net-(TS24-OUT)") (class "Default")
      (node (ref "R24") (pin "2") (pinfunction "2_2") (pintype "passive"))
      (node (ref "TS24") (pin "3") (pinfunction "OUT_3") (pintype "passive"))
    )
    (net (code "65") (name "Net-(TS25-OUT)") (class "Default")
      (node (ref "R25") (pin "2") (pinfunction "2_2") (pintype "passive"))
      (node (ref "TS25") (pin "3") (pinfunction "OUT_3") (pintype "passive"))
    )
    (net (code "66") (name "Net-(TS26-OUT)") (class "Default")
      (node (ref "R26") (pin "2") (pinfunction "2_2") (pintype "passive"))
      (node (ref "TS26") (pin "3") (pinfunction "OUT_3") (pintype "passive"))
    )
    (net (code "67") (name "Net-(TS27-OUT)") (class "Default")
      (node (ref "R27") (pin "2") (pinfunction "2_2") (pintype "passive"))
      (node (ref "TS27") (pin "3") (pinfunction "OUT_3") (pintype "passive"))
    )
    (net (code "68") (name "Net-(TS28-OUT)") (class "Default")
      (node (ref "R28") (pin "2") (pinfunction "2_2") (pintype "passive"))
      (node (ref "TS28") (pin "3") (pinfunction "OUT_3") (pintype "passive"))
    )
    (net (code "69") (name "Net-(TS29-OUT)") (class "Default")
      (node (ref "R29") (pin "2") (pinfunction "2_2") (pintype "passive"))
      (node (ref "TS29") (pin "3") (pinfunction "OUT_3") (pintype "passive"))
    )
    (net (code "70") (name "Net-(TS30-OUT)") (class "Default")
      (node (ref "R30") (pin "2") (pinfunction "2_2") (pintype "passive"))
      (node (ref "TS30") (pin "3") (pinfunction "OUT_3") (pintype "passive"))
    )
    (net (code "71") (name "Net-(TS31-OUT)") (class "Default")
      (node (ref "R31") (pin "2") (pinfunction "2_2") (pintype "passive"))
      (node (ref "TS31") (pin "3") (pinfunction "OUT_3") (pintype "passive"))
    )
    (net (code "72") (name "Net-(TS32-OUT)") (class "Default")
      (node (ref "R32") (pin "2") (pinfunction "2_2") (pintype "passive"))
      (node (ref "TS32") (pin "3") (pinfunction "OUT_3") (pintype "passive"))
    )
    (net (code "73") (name "VCC") (class "Default")
      (node (ref "C33") (pin "2") (pinfunction "2_2") (pintype "passive"))
      (node (ref "C34") (pin "2") (pinfunction "2_2") (pintype "passive"))
      (node (ref "C35") (pin "2") (pinfunction "2_2") (pintype "passive"))
      (node (ref "HL1") (pin "2") (pinfunction "A_2") (pintype "passive"))
      (node (ref "MUX1") (pin "24") (pinfunction "VCC_24") (pintype "power_in"))
      (node (ref "MUX2") (pin "24") (pinfunction "VCC_24") (pintype "power_in"))
      (node (ref "TS1") (pin "1") (pinfunction "VCC_1") (pintype "passive"))
      (node (ref "TS10") (pin "1") (pinfunction "VCC_1") (pintype "passive"))
      (node (ref "TS11") (pin "1") (pinfunction "VCC_1") (pintype "passive"))
      (node (ref "TS12") (pin "1") (pinfunction "VCC_1") (pintype "passive"))
      (node (ref "TS13") (pin "1") (pinfunction "VCC_1") (pintype "passive"))
      (node (ref "TS14") (pin "1") (pinfunction "VCC_1") (pintype "passive"))
      (node (ref "TS15") (pin "1") (pinfunction "VCC_1") (pintype "passive"))
      (node (ref "TS16") (pin "1") (pinfunction "VCC_1") (pintype "passive"))
      (node (ref "TS17") (pin "1") (pinfunction "VCC_1") (pintype "passive"))
      (node (ref "TS18") (pin "1") (pinfunction "VCC_1") (pintype "passive"))
      (node (ref "TS19") (pin "1") (pinfunction "VCC_1") (pintype "passive"))
      (node (ref "TS2") (pin "1") (pinfunction "VCC_1") (pintype "passive"))
      (node (ref "TS20") (pin "1") (pinfunction "VCC_1") (pintype "passive"))
      (node (ref "TS21") (pin "1") (pinfunction "VCC_1") (pintype "passive"))
      (node (ref "TS22") (pin "1") (pinfunction "VCC_1") (pintype "passive"))
      (node (ref "TS23") (pin "1") (pinfunction "VCC_1") (pintype "passive"))
      (node (ref "TS24") (pin "1") (pinfunction "VCC_1") (pintype "passive"))
      (node (ref "TS25") (pin "1") (pinfunction "VCC_1") (pintype "passive"))
      (node (ref "TS26") (pin "1") (pinfunction "VCC_1") (pintype "passive"))
      (node (ref "TS27") (pin "1") (pinfunction "VCC_1") (pintype "passive"))
      (node (ref "TS28") (pin "1") (pinfunction "VCC_1") (pintype "passive"))
      (node (ref "TS29") (pin "1") (pinfunction "VCC_1") (pintype "passive"))
      (node (ref "TS3") (pin "1") (pinfunction "VCC_1") (pintype "passive"))
      (node (ref "TS30") (pin "1") (pinfunction "VCC_1") (pintype "passive"))
      (node (ref "TS31") (pin "1") (pinfunction "VCC_1") (pintype "passive"))
      (node (ref "TS32") (pin "1") (pinfunction "VCC_1") (pintype "passive"))
      (node (ref "TS4") (pin "1") (pinfunction "VCC_1") (pintype "passive"))
      (node (ref "TS5") (pin "1") (pinfunction "VCC_1") (pintype "passive"))
      (node (ref "TS6") (pin "1") (pinfunction "VCC_1") (pintype "passive"))
      (node (ref "TS7") (pin "1") (pinfunction "VCC_1") (pintype "passive"))
      (node (ref "TS8") (pin "1") (pinfunction "VCC_1") (pintype "passive"))
      (node (ref "TS9") (pin "1") (pinfunction "VCC_1") (pintype "passive"))
      (node (ref "XP1") (pin "8") (pinfunction "8_8") (pintype "passive"))
    )
  )
)
